# Powersupply.net
KiCad netlist of a schematic drawn in EAGLE
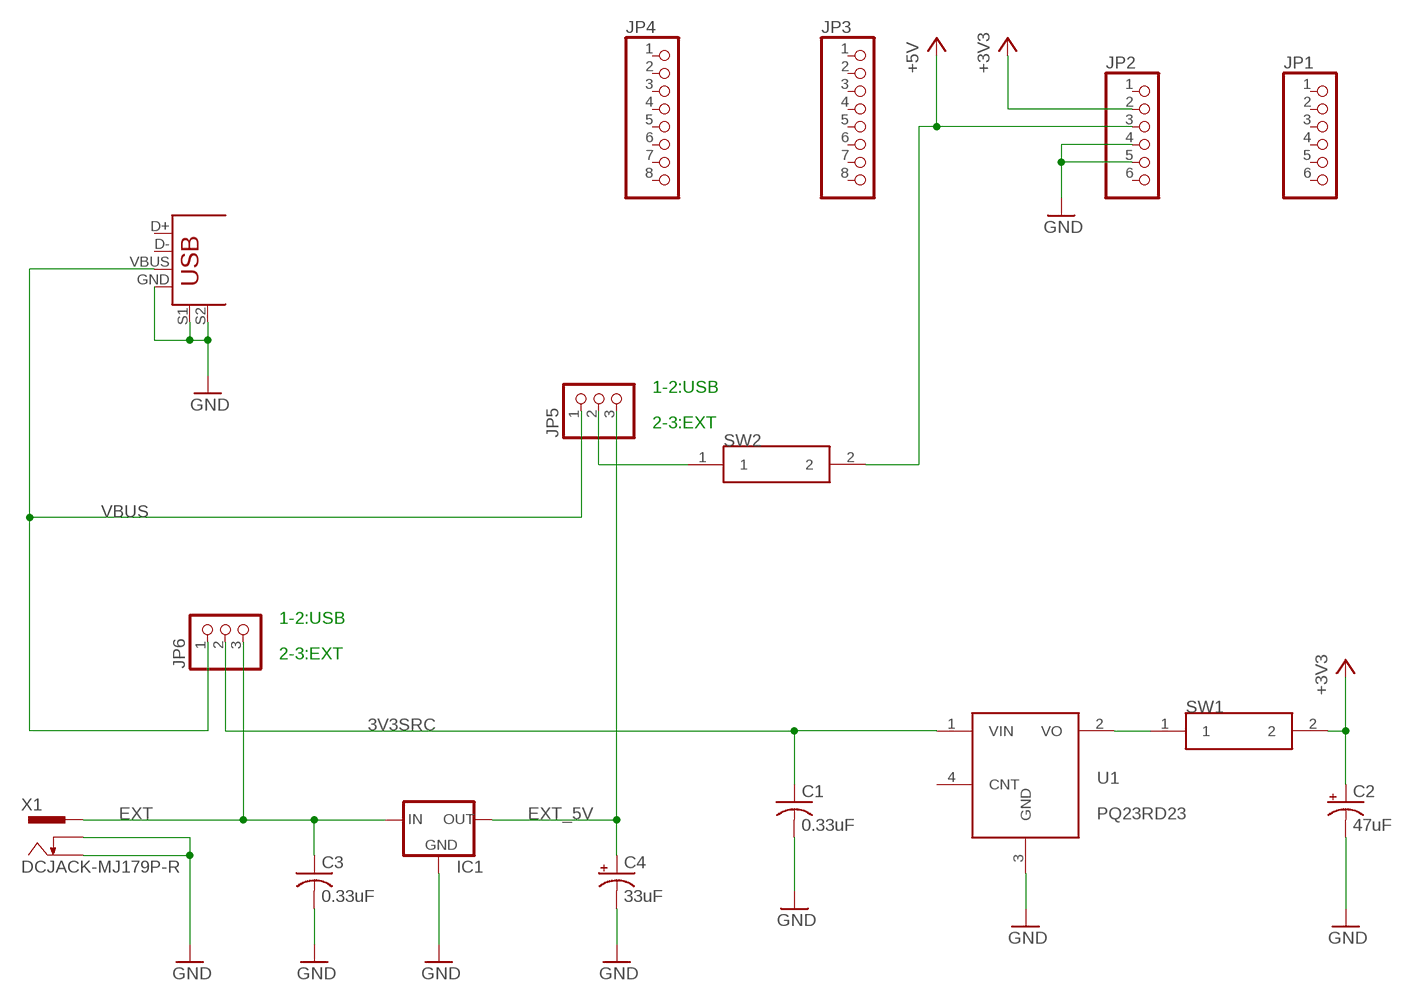
[diagram p0: schematic, sheet 1]

(export (version "E")
  (design (tool "Eeschema 10.0.6"))
  (components
    (comp (ref "C1")
      (value "0.33uF")
      (footprint "eagle-import:C025-040X050")
      (libsource (lib "eagle-import") (part "CAP"))
    )
    (comp (ref "C2")
      (value "47uF")
      (footprint "eagle-import:CPOL-US")
      (libsource (lib "eagle-import") (part "CPOL-US"))
    )
    (comp (ref "C3")
      (value "0.33uF")
      (footprint "eagle-import:C025-040X050")
      (libsource (lib "eagle-import") (part "CAP"))
    )
    (comp (ref "C4")
      (value "33uF")
      (footprint "eagle-import:CPOL-US")
      (libsource (lib "eagle-import") (part "CPOL-US"))
    )
    (comp (ref "IC1")
      (value "78XXL")
      (footprint "eagle-import:78XXL")
      (libsource (lib "eagle-import") (part "78XXL"))
    )
    (comp (ref "JP1")
      (value "PINHD-1X6")
      (footprint "eagle-import:1X06")
      (libsource (lib "eagle-import") (part "PINHD-1X6"))
    )
    (comp (ref "JP2")
      (value "PINHD-1X6")
      (footprint "eagle-import:1X06")
      (libsource (lib "eagle-import") (part "PINHD-1X6"))
    )
    (comp (ref "JP3")
      (value "PINHD-1X8")
      (footprint "eagle-import:1X08")
      (libsource (lib "eagle-import") (part "PINHD-1X8"))
    )
    (comp (ref "JP4")
      (value "PINHD-1X8")
      (footprint "eagle-import:1X08")
      (libsource (lib "eagle-import") (part "PINHD-1X8"))
    )
    (comp (ref "JP5")
      (value "PINHD-1X3")
      (footprint "eagle-import:1X03")
      (libsource (lib "eagle-import") (part "PINHD-1X3"))
    )
    (comp (ref "JP6")
      (value "PINHD-1X3")
      (footprint "eagle-import:1X03")
      (libsource (lib "eagle-import") (part "PINHD-1X3"))
    )
    (comp (ref "SW1")
      (value "POLYSWITCH")
      (footprint "eagle-import:POLYSWITCH")
      (libsource (lib "eagle-import") (part "POLYSWITCH"))
    )
    (comp (ref "SW2")
      (value "POLYSWITCH")
      (footprint "eagle-import:POLYSWITCH")
      (libsource (lib "eagle-import") (part "POLYSWITCH"))
    )
    (comp (ref "U$1")
      (value "USB+SHIELD")
      (footprint "eagle-import:USB-B-PTH")
      (libsource (lib "eagle-import") (part "USB+SHIELD"))
    )
    (comp (ref "U1")
      (value "PQ23RD23")
      (footprint "eagle-import:PQ3RD23")
      (libsource (lib "eagle-import") (part "PQ23RD23"))
    )
    (comp (ref "X1")
      (value "DCJACK-MJ179P-R")
      (footprint "eagle-import:MJ-179P-R")
      (libsource (lib "eagle-import") (part "DCJACK-MJ179P-R"))
    )
  )
  (nets
    (net (code "1") (name "+3V3") (class "Default")
      (node (ref "C2") (pin "+") (pinfunction "+_+") (pintype "passive"))
      (node (ref "JP2") (pin "2") (pinfunction "2_2") (pintype "passive"))
      (node (ref "SW1") (pin "2") (pinfunction "2_2") (pintype "passive"))
    )
    (net (code "2") (name "+5V") (class "Default")
      (node (ref "JP2") (pin "3") (pinfunction "3_3") (pintype "passive"))
      (node (ref "SW2") (pin "2") (pinfunction "2_2") (pintype "passive"))
    )
    (net (code "3") (name "/3V3SRC") (class "Default")
      (node (ref "C1") (pin "1") (pinfunction "1_1") (pintype "passive"))
      (node (ref "JP6") (pin "2") (pinfunction "2_2") (pintype "passive"))
      (node (ref "U1") (pin "1") (pinfunction "VIN_1") (pintype "power_in"))
    )
    (net (code "4") (name "/EXT") (class "Default")
      (node (ref "C3") (pin "1") (pinfunction "1_1") (pintype "passive"))
      (node (ref "IC1") (pin "IN") (pinfunction "IN_IN") (pintype "input"))
      (node (ref "JP6") (pin "3") (pinfunction "3_3") (pintype "passive"))
      (node (ref "X1") (pin "1") (pinfunction "1_1") (pintype "passive"))
    )
    (net (code "5") (name "/EXT_5V") (class "Default")
      (node (ref "C4") (pin "+") (pinfunction "+_+") (pintype "passive"))
      (node (ref "IC1") (pin "OUT") (pinfunction "OUT_OUT") (pintype "passive"))
      (node (ref "JP5") (pin "3") (pinfunction "3_3") (pintype "passive"))
    )
    (net (code "6") (name "/VBUS") (class "Default")
      (node (ref "JP5") (pin "1") (pinfunction "1_1") (pintype "passive"))
      (node (ref "JP6") (pin "1") (pinfunction "1_1") (pintype "passive"))
      (node (ref "U$1") (pin "VBUS") (pinfunction "VBUS_VBUS") (pintype "bidirectional"))
    )
    (net (code "7") (name "GND") (class "Default")
      (node (ref "C1") (pin "2") (pinfunction "2_2") (pintype "passive"))
      (node (ref "C2") (pin "-") (pinfunction "-_-") (pintype "passive"))
      (node (ref "C3") (pin "2") (pinfunction "2_2") (pintype "passive"))
      (node (ref "C4") (pin "-") (pinfunction "-_-") (pintype "passive"))
      (node (ref "IC1") (pin "GND") (pinfunction "GND_GND") (pintype "input"))
      (node (ref "JP2") (pin "4") (pinfunction "4_4") (pintype "passive"))
      (node (ref "JP2") (pin "5") (pinfunction "5_5") (pintype "passive"))
      (node (ref "U$1") (pin "GND") (pinfunction "GND_GND") (pintype "bidirectional"))
      (node (ref "U$1") (pin "S1") (pinfunction "P$1_S1") (pintype "bidirectional"))
      (node (ref "U$1") (pin "S2") (pinfunction "P$2_S2") (pintype "bidirectional"))
      (node (ref "U1") (pin "3") (pinfunction "GND_3") (pintype "power_in"))
      (node (ref "X1") (pin "2") (pinfunction "2_2") (pintype "passive"))
      (node (ref "X1") (pin "3") (pinfunction "3_3") (pintype "passive"))
    )
    (net (code "8") (name "Net-(JP5-Pad2)") (class "Default")
      (node (ref "JP5") (pin "2") (pinfunction "2_2") (pintype "passive"))
      (node (ref "SW2") (pin "1") (pinfunction "1_1") (pintype "passive"))
    )
    (net (code "9") (name "Net-(U1-VO)") (class "Default")
      (node (ref "SW1") (pin "1") (pinfunction "1_1") (pintype "passive"))
      (node (ref "U1") (pin "2") (pinfunction "VO_2") (pintype "passive"))
    )
    (net (code "10") (name "unconnected-(JP1-Pad1)") (class "Default")
      (node (ref "JP1") (pin "1") (pinfunction "1_1") (pintype "passive"))
    )
    (net (code "11") (name "unconnected-(JP1-Pad2)") (class "Default")
      (node (ref "JP1") (pin "2") (pinfunction "2_2") (pintype "passive"))
    )
    (net (code "12") (name "unconnected-(JP1-Pad3)") (class "Default")
      (node (ref "JP1") (pin "3") (pinfunction "3_3") (pintype "passive"))
    )
    (net (code "13") (name "unconnected-(JP1-Pad4)") (class "Default")
      (node (ref "JP1") (pin "4") (pinfunction "4_4") (pintype "passive"))
    )
    (net (code "14") (name "unconnected-(JP1-Pad5)") (class "Default")
      (node (ref "JP1") (pin "5") (pinfunction "5_5") (pintype "passive"))
    )
    (net (code "15") (name "unconnected-(JP1-Pad6)") (class "Default")
      (node (ref "JP1") (pin "6") (pinfunction "6_6") (pintype "passive"))
    )
    (net (code "16") (name "unconnected-(JP2-Pad1)") (class "Default")
      (node (ref "JP2") (pin "1") (pinfunction "1_1") (pintype "passive"))
    )
    (net (code "17") (name "unconnected-(JP2-Pad6)") (class "Default")
      (node (ref "JP2") (pin "6") (pinfunction "6_6") (pintype "passive"))
    )
    (net (code "18") (name "unconnected-(JP3-Pad1)") (class "Default")
      (node (ref "JP3") (pin "1") (pinfunction "1_1") (pintype "passive"))
    )
    (net (code "19") (name "unconnected-(JP3-Pad2)") (class "Default")
      (node (ref "JP3") (pin "2") (pinfunction "2_2") (pintype "passive"))
    )
    (net (code "20") (name "unconnected-(JP3-Pad3)") (class "Default")
      (node (ref "JP3") (pin "3") (pinfunction "3_3") (pintype "passive"))
    )
    (net (code "21") (name "unconnected-(JP3-Pad4)") (class "Default")
      (node (ref "JP3") (pin "4") (pinfunction "4_4") (pintype "passive"))
    )
    (net (code "22") (name "unconnected-(JP3-Pad5)") (class "Default")
      (node (ref "JP3") (pin "5") (pinfunction "5_5") (pintype "passive"))
    )
    (net (code "23") (name "unconnected-(JP3-Pad6)") (class "Default")
      (node (ref "JP3") (pin "6") (pinfunction "6_6") (pintype "passive"))
    )
    (net (code "24") (name "unconnected-(JP3-Pad7)") (class "Default")
      (node (ref "JP3") (pin "7") (pinfunction "7_7") (pintype "passive"))
    )
    (net (code "25") (name "unconnected-(JP3-Pad8)") (class "Default")
      (node (ref "JP3") (pin "8") (pinfunction "8_8") (pintype "passive"))
    )
    (net (code "26") (name "unconnected-(JP4-Pad1)") (class "Default")
      (node (ref "JP4") (pin "1") (pinfunction "1_1") (pintype "passive"))
    )
    (net (code "27") (name "unconnected-(JP4-Pad2)") (class "Default")
      (node (ref "JP4") (pin "2") (pinfunction "2_2") (pintype "passive"))
    )
    (net (code "28") (name "unconnected-(JP4-Pad3)") (class "Default")
      (node (ref "JP4") (pin "3") (pinfunction "3_3") (pintype "passive"))
    )
    (net (code "29") (name "unconnected-(JP4-Pad4)") (class "Default")
      (node (ref "JP4") (pin "4") (pinfunction "4_4") (pintype "passive"))
    )
    (net (code "30") (name "unconnected-(JP4-Pad5)") (class "Default")
      (node (ref "JP4") (pin "5") (pinfunction "5_5") (pintype "passive"))
    )
    (net (code "31") (name "unconnected-(JP4-Pad6)") (class "Default")
      (node (ref "JP4") (pin "6") (pinfunction "6_6") (pintype "passive"))
    )
    (net (code "32") (name "unconnected-(JP4-Pad7)") (class "Default")
      (node (ref "JP4") (pin "7") (pinfunction "7_7") (pintype "passive"))
    )
    (net (code "33") (name "unconnected-(JP4-Pad8)") (class "Default")
      (node (ref "JP4") (pin "8") (pinfunction "8_8") (pintype "passive"))
    )
    (net (code "34") (name "unconnected-(U$1-PadD+)") (class "Default")
      (node (ref "U$1") (pin "D+") (pinfunction "D+_D+") (pintype "bidirectional"))
    )
    (net (code "35") (name "unconnected-(U$1-PadD-)") (class "Default")
      (node (ref "U$1") (pin "D-") (pinfunction "D-_D-") (pintype "bidirectional"))
    )
    (net (code "36") (name "unconnected-(U1-CNT-Pad4)") (class "Default")
      (node (ref "U1") (pin "4") (pinfunction "CNT_4") (pintype "input"))
    )
  )
)
